# 6ButtonSMDVerteiler.net
KiCad netlist of a schematic drawn in EAGLE
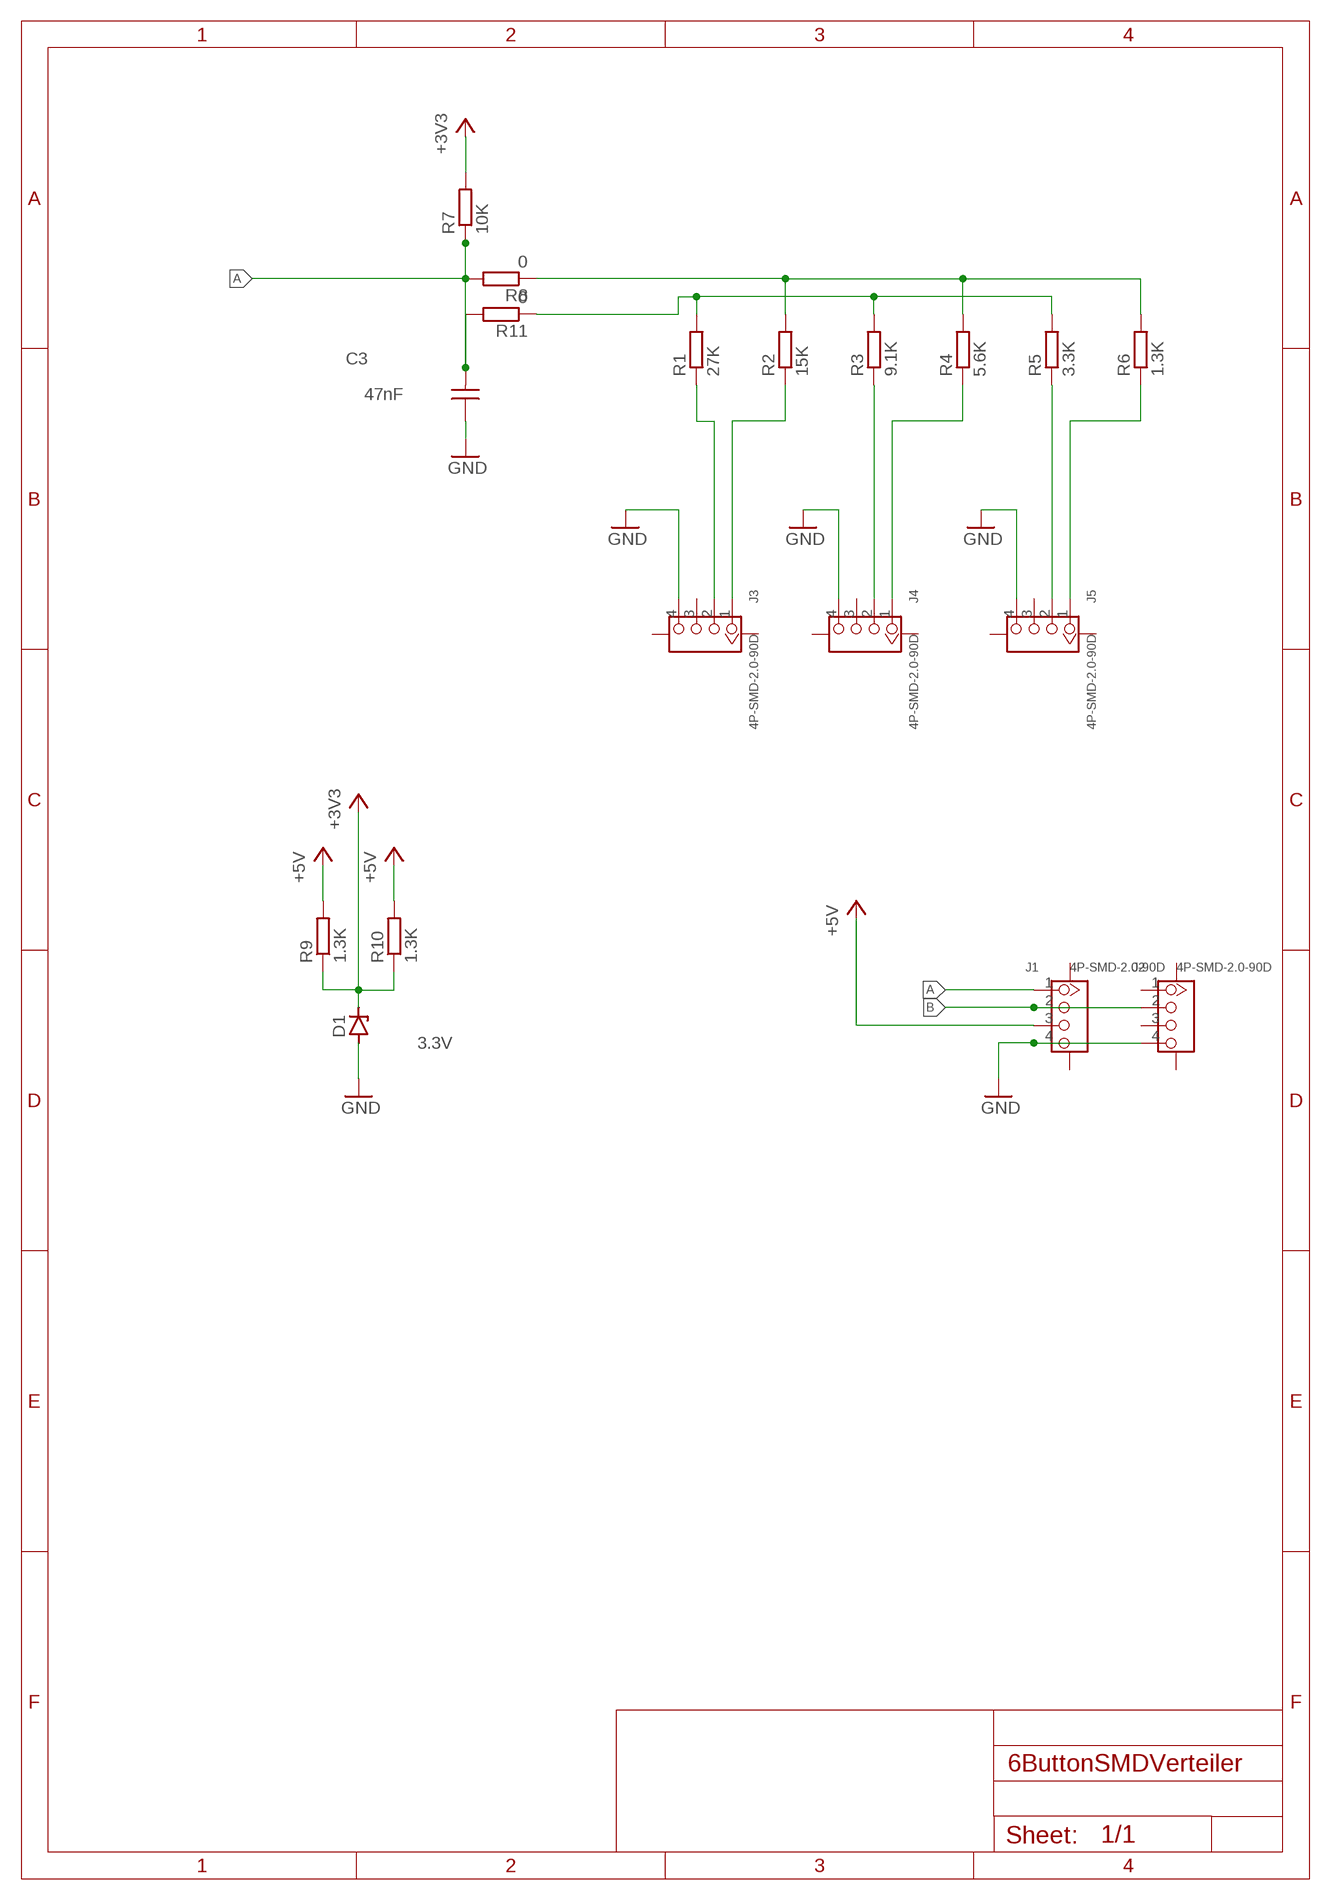
[diagram p0: schematic, sheet 1]

(export (version "E")
  (design (tool "Eeschema 10.0.6"))
  (components
    (comp (ref "C3")
      (value "47nF")
      (footprint "eagle-import:WCAP-CSGP_1206_H0.8")
      (libsource (lib "eagle-import") (part "WCAP-CSGP_1206_H0.8_50V(DC)_885012208085"))
    )
    (comp (ref "D1")
      (value "3.3V")
      (footprint "eagle-import:SOD80C")
      (libsource (lib "eagle-import") (part "ZENER-DIODESOD80C"))
    )
    (comp (ref "J1")
      (value "4P-SMD-2.0-90D")
      (footprint "eagle-import:HW4-SMD-2.0-90D")
      (libsource (lib "eagle-import") (part "GROVE-CONNECTOR-SMD-90D(4+2P-2.0)"))
    )
    (comp (ref "J2")
      (value "4P-SMD-2.0-90D")
      (footprint "eagle-import:HW4-SMD-2.0-90D")
      (libsource (lib "eagle-import") (part "GROVE-CONNECTOR-SMD-90D(4+2P-2.0)"))
    )
    (comp (ref "J3")
      (value "4P-SMD-2.0-90D")
      (footprint "eagle-import:HW4-SMD-2.0-90D")
      (libsource (lib "eagle-import") (part "GROVE-CONNECTOR-SMD-90D(4+2P-2.0)"))
    )
    (comp (ref "J4")
      (value "4P-SMD-2.0-90D")
      (footprint "eagle-import:HW4-SMD-2.0-90D")
      (libsource (lib "eagle-import") (part "GROVE-CONNECTOR-SMD-90D(4+2P-2.0)"))
    )
    (comp (ref "J5")
      (value "4P-SMD-2.0-90D")
      (footprint "eagle-import:HW4-SMD-2.0-90D")
      (libsource (lib "eagle-import") (part "GROVE-CONNECTOR-SMD-90D(4+2P-2.0)"))
    )
    (comp (ref "R1")
      (value "27K")
      (footprint "eagle-import:R1206")
      (libsource (lib "eagle-import") (part "R-EU_R1206"))
    )
    (comp (ref "R2")
      (value "15K")
      (footprint "eagle-import:R1206")
      (libsource (lib "eagle-import") (part "R-EU_R1206"))
    )
    (comp (ref "R3")
      (value "9.1K")
      (footprint "eagle-import:R1206")
      (libsource (lib "eagle-import") (part "R-EU_R1206"))
    )
    (comp (ref "R4")
      (value "5.6K")
      (footprint "eagle-import:R1206")
      (libsource (lib "eagle-import") (part "R-EU_R1206"))
    )
    (comp (ref "R5")
      (value "3.3K")
      (footprint "eagle-import:R1206")
      (libsource (lib "eagle-import") (part "R-EU_R1206"))
    )
    (comp (ref "R6")
      (value "1.3K")
      (footprint "eagle-import:R1206")
      (libsource (lib "eagle-import") (part "R-EU_R1206"))
    )
    (comp (ref "R7")
      (value "10K")
      (footprint "eagle-import:R1206")
      (libsource (lib "eagle-import") (part "R-EU_R1206"))
    )
    (comp (ref "R8")
      (value "0")
      (footprint "eagle-import:R1206")
      (libsource (lib "eagle-import") (part "R-EU_R1206"))
    )
    (comp (ref "R9")
      (value "1.3K")
      (footprint "eagle-import:R1206")
      (libsource (lib "eagle-import") (part "R-EU_R1206"))
    )
    (comp (ref "R10")
      (value "1.3K")
      (footprint "eagle-import:R1206")
      (libsource (lib "eagle-import") (part "R-EU_R1206"))
    )
    (comp (ref "R11")
      (value "0")
      (footprint "eagle-import:R1206")
      (libsource (lib "eagle-import") (part "R-EU_R1206"))
    )
  )
  (nets
    (net (code "1") (name "+3V3") (class "Default")
      (node (ref "D1") (pin "C") (pinfunction "C_C") (pintype "passive"))
      (node (ref "R10") (pin "1") (pinfunction "1_1") (pintype "passive"))
      (node (ref "R7") (pin "2") (pinfunction "2_2") (pintype "passive"))
      (node (ref "R9") (pin "1") (pinfunction "1_1") (pintype "passive"))
    )
    (net (code "2") (name "+5V") (class "Default")
      (node (ref "J1") (pin "3") (pinfunction "3_3") (pintype "bidirectional"))
      (node (ref "R10") (pin "2") (pinfunction "2_2") (pintype "passive"))
      (node (ref "R9") (pin "2") (pinfunction "2_2") (pintype "passive"))
    )
    (net (code "3") (name "A") (class "Default")
      (node (ref "C3") (pin "2") (pinfunction "2_2") (pintype "passive"))
      (node (ref "J1") (pin "1") (pinfunction "1_1") (pintype "bidirectional"))
      (node (ref "R11") (pin "2") (pinfunction "2_2") (pintype "passive"))
      (node (ref "R7") (pin "1") (pinfunction "1_1") (pintype "passive"))
      (node (ref "R8") (pin "2") (pinfunction "2_2") (pintype "passive"))
    )
    (net (code "4") (name "B") (class "Default")
      (node (ref "J1") (pin "2") (pinfunction "2_2") (pintype "bidirectional"))
      (node (ref "J2") (pin "2") (pinfunction "2_2") (pintype "bidirectional"))
    )
    (net (code "5") (name "GND") (class "Default")
      (node (ref "C3") (pin "1") (pinfunction "1_1") (pintype "passive"))
      (node (ref "D1") (pin "A") (pinfunction "A_A") (pintype "passive"))
      (node (ref "J1") (pin "4") (pinfunction "4_4") (pintype "bidirectional"))
      (node (ref "J2") (pin "4") (pinfunction "4_4") (pintype "bidirectional"))
      (node (ref "J3") (pin "4") (pinfunction "4_4") (pintype "bidirectional"))
      (node (ref "J4") (pin "4") (pinfunction "4_4") (pintype "bidirectional"))
      (node (ref "J5") (pin "4") (pinfunction "4_4") (pintype "bidirectional"))
    )
    (net (code "6") (name "Net-(J3-Pad1)") (class "Default")
      (node (ref "J3") (pin "1") (pinfunction "1_1") (pintype "bidirectional"))
      (node (ref "R2") (pin "1") (pinfunction "1_1") (pintype "passive"))
    )
    (net (code "7") (name "Net-(J3-Pad2)") (class "Default")
      (node (ref "J3") (pin "2") (pinfunction "2_2") (pintype "bidirectional"))
      (node (ref "R1") (pin "1") (pinfunction "1_1") (pintype "passive"))
    )
    (net (code "8") (name "Net-(J4-Pad1)") (class "Default")
      (node (ref "J4") (pin "1") (pinfunction "1_1") (pintype "bidirectional"))
      (node (ref "R4") (pin "1") (pinfunction "1_1") (pintype "passive"))
    )
    (net (code "9") (name "Net-(J4-Pad2)") (class "Default")
      (node (ref "J4") (pin "2") (pinfunction "2_2") (pintype "bidirectional"))
      (node (ref "R3") (pin "1") (pinfunction "1_1") (pintype "passive"))
    )
    (net (code "10") (name "Net-(J5-Pad1)") (class "Default")
      (node (ref "J5") (pin "1") (pinfunction "1_1") (pintype "bidirectional"))
      (node (ref "R6") (pin "1") (pinfunction "1_1") (pintype "passive"))
    )
    (net (code "11") (name "Net-(J5-Pad2)") (class "Default")
      (node (ref "J5") (pin "2") (pinfunction "2_2") (pintype "bidirectional"))
      (node (ref "R5") (pin "1") (pinfunction "1_1") (pintype "passive"))
    )
    (net (code "12") (name "Net-(R1-Pad2)") (class "Default")
      (node (ref "R1") (pin "2") (pinfunction "2_2") (pintype "passive"))
      (node (ref "R11") (pin "1") (pinfunction "1_1") (pintype "passive"))
      (node (ref "R3") (pin "2") (pinfunction "2_2") (pintype "passive"))
      (node (ref "R5") (pin "2") (pinfunction "2_2") (pintype "passive"))
    )
    (net (code "13") (name "Net-(R2-Pad2)") (class "Default")
      (node (ref "R2") (pin "2") (pinfunction "2_2") (pintype "passive"))
      (node (ref "R4") (pin "2") (pinfunction "2_2") (pintype "passive"))
      (node (ref "R6") (pin "2") (pinfunction "2_2") (pintype "passive"))
      (node (ref "R8") (pin "1") (pinfunction "1_1") (pintype "passive"))
    )
    (net (code "14") (name "unconnected-(J1-PadSS1)") (class "Default")
      (node (ref "J1") (pin "SS1") (pinfunction "SS1_SS1") (pintype "bidirectional"))
    )
    (net (code "15") (name "unconnected-(J1-PadSS2)") (class "Default")
      (node (ref "J1") (pin "SS2") (pinfunction "SS2_SS2") (pintype "bidirectional"))
    )
    (net (code "16") (name "unconnected-(J2-Pad1)") (class "Default")
      (node (ref "J2") (pin "1") (pinfunction "1_1") (pintype "bidirectional"))
    )
    (net (code "17") (name "unconnected-(J2-Pad3)") (class "Default")
      (node (ref "J2") (pin "3") (pinfunction "3_3") (pintype "bidirectional"))
    )
    (net (code "18") (name "unconnected-(J2-PadSS1)") (class "Default")
      (node (ref "J2") (pin "SS1") (pinfunction "SS1_SS1") (pintype "bidirectional"))
    )
    (net (code "19") (name "unconnected-(J2-PadSS2)") (class "Default")
      (node (ref "J2") (pin "SS2") (pinfunction "SS2_SS2") (pintype "bidirectional"))
    )
    (net (code "20") (name "unconnected-(J3-Pad3)") (class "Default")
      (node (ref "J3") (pin "3") (pinfunction "3_3") (pintype "bidirectional"))
    )
    (net (code "21") (name "unconnected-(J3-PadSS1)") (class "Default")
      (node (ref "J3") (pin "SS1") (pinfunction "SS1_SS1") (pintype "bidirectional"))
    )
    (net (code "22") (name "unconnected-(J3-PadSS2)") (class "Default")
      (node (ref "J3") (pin "SS2") (pinfunction "SS2_SS2") (pintype "bidirectional"))
    )
    (net (code "23") (name "unconnected-(J4-Pad3)") (class "Default")
      (node (ref "J4") (pin "3") (pinfunction "3_3") (pintype "bidirectional"))
    )
    (net (code "24") (name "unconnected-(J4-PadSS1)") (class "Default")
      (node (ref "J4") (pin "SS1") (pinfunction "SS1_SS1") (pintype "bidirectional"))
    )
    (net (code "25") (name "unconnected-(J4-PadSS2)") (class "Default")
      (node (ref "J4") (pin "SS2") (pinfunction "SS2_SS2") (pintype "bidirectional"))
    )
    (net (code "26") (name "unconnected-(J5-Pad3)") (class "Default")
      (node (ref "J5") (pin "3") (pinfunction "3_3") (pintype "bidirectional"))
    )
    (net (code "27") (name "unconnected-(J5-PadSS1)") (class "Default")
      (node (ref "J5") (pin "SS1") (pinfunction "SS1_SS1") (pintype "bidirectional"))
    )
    (net (code "28") (name "unconnected-(J5-PadSS2)") (class "Default")
      (node (ref "J5") (pin "SS2") (pinfunction "SS2_SS2") (pintype "bidirectional"))
    )
  )
)
